# 05_-_Power_Supply.net
KiCad netlist of a schematic drawn in Altium Designer
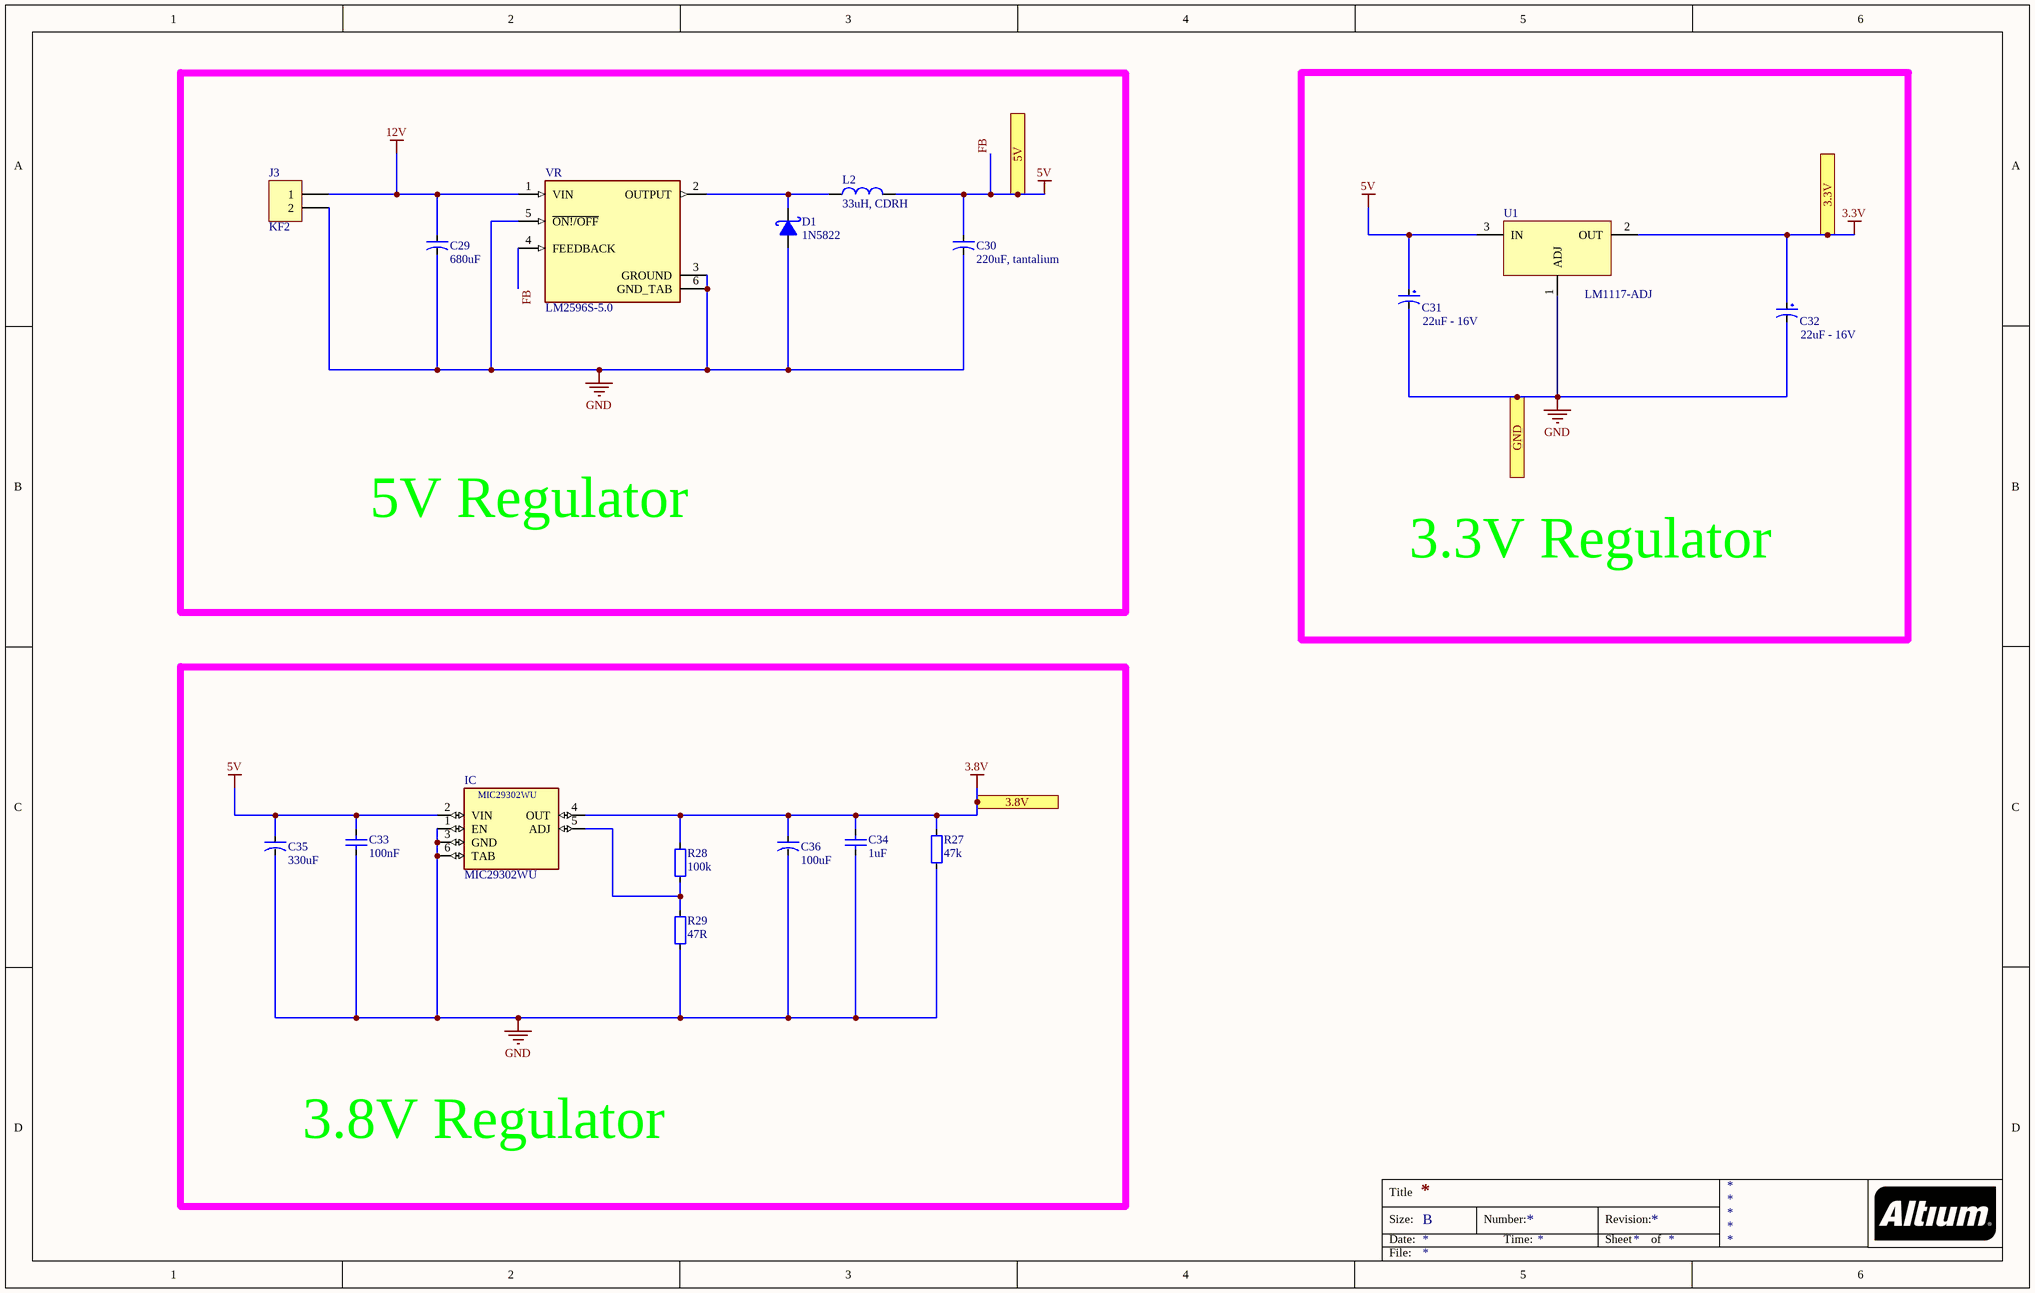
[diagram p0: [05] - Power Supply.SchDoc]

(export (version "E")
  (design (tool "Eeschema 10.0.6"))
  (components
    (comp (ref "C29")
      (value "680uF")
      (footprint "CAP-ALU-SMD-D")
      (description "Polarized Capacitor (Axial)")
      (fields (field (name "PUBLISHER") "Altium Limited"))
      (libsource (lib "My Library") (part "CAP-ALU-SMD"))
    )
    (comp (ref "C30")
      (value "220uF, tantalium")
      (footprint "CAP-ALU-SMD-D")
      (description "Polarized Capacitor (Axial)")
      (fields (field (name "PUBLISHER") "Altium Limited"))
      (libsource (lib "My Library") (part "CAP-ALU-SMD"))
    )
    (comp (ref "C31")
      (value "22uF - 16V")
      (footprint "CAP-ALU-SMD-D")
      (description "Capacitor ALU SMD")
      (libsource (lib "HS_Lib") (part "Cap_ALU_Smd"))
    )
    (comp (ref "C32")
      (value "22uF - 16V")
      (footprint "CAP-ALU-SMD-D")
      (description "Capacitor ALU SMD")
      (libsource (lib "HS_Lib") (part "Cap_ALU_Smd"))
    )
    (comp (ref "C33")
      (value "100nF")
      (footprint "CAP_0805")
      (description "Capacitor")
      (fields (field (name "PUBLISHER") "Altium Limited"))
      (libsource (lib "My Library") (part "CapSMD"))
    )
    (comp (ref "C34")
      (value "1uF")
      (footprint "CAP_0805")
      (description "Capacitor")
      (fields (field (name "PUBLISHER") "Altium Limited"))
      (libsource (lib "My Library") (part "CapSMD"))
    )
    (comp (ref "C35")
      (value "330uF")
      (footprint "CAP-ALU-SMD-D")
      (description "Polarized Capacitor (Axial)")
      (fields (field (name "PUBLISHER") "Altium Limited"))
      (libsource (lib "My Library") (part "CAP-ALU-SMD"))
    )
    (comp (ref "C36")
      (value "100uF")
      (footprint "CAP-ALU-SMD-D")
      (description "Polarized Capacitor (Axial)")
      (fields (field (name "PUBLISHER") "Altium Limited"))
      (libsource (lib "My Library") (part "CAP-ALU-SMD"))
    )
    (comp (ref "D1")
      (value "1N5822")
      (footprint "B560C-13-F")
      (description "Schottky Rectifiers")
      (libsource (lib "My Library") (part "1N5822"))
    )
    (comp (ref "IC")
      (value "MIC29302WU")
      (footprint "TO-263")
      (description "Linear Voltage Regulator IC 1 Output 3A TO-263-5")
      (fields (field (name "MF") "Microchip Technology"))
      (libsource (lib "My Library") (part "MIC29302WU"))
    )
    (comp (ref "J3")
      (value "KF2")
      (footprint "KF2-7.62")
      (fields
        (field (name "MANUFACTURER") "Würth Elektronik eiSos GmbH")
        (field (name "PARTNO") "691103110002")
        (field (name "CREATED BY") "Karrer Zheng")
      )
      (libsource (lib "My Library") (part "KF2"))
    )
    (comp (ref "L2")
      (value "33uH, CDRH")
      (footprint "Inductor_SMD")
      (description "Inductor")
      (libsource (lib "My Library") (part "L1"))
    )
    (comp (ref "R27")
      (value "47k")
      (footprint "RES-SMD-0603")
      (description "Resistor")
      (fields
        (field (name "MANUFACTURER") "Generic Components")
        (field (name "PUBLISHER") "Altium Hobart Technology Centre")
      )
      (libsource (lib "HS_Lib") (part "Resistor - SMD"))
    )
    (comp (ref "R28")
      (value "100k")
      (footprint "RES-SMD-0603")
      (description "Resistor")
      (fields
        (field (name "MANUFACTURER") "Generic Components")
        (field (name "PUBLISHER") "Altium Hobart Technology Centre")
      )
      (libsource (lib "HS_Lib") (part "Resistor - SMD"))
    )
    (comp (ref "R29")
      (value "47R")
      (footprint "RES-SMD-0603")
      (description "Resistor")
      (fields
        (field (name "MANUFACTURER") "Generic Components")
        (field (name "PUBLISHER") "Altium Hobart Technology Centre")
      )
      (libsource (lib "HS_Lib") (part "Resistor - SMD"))
    )
    (comp (ref "U1")
      (value "LM1117-ADJ")
      (footprint "LM1117-SOP")
      (description "800mA Low-Dropout Linear Regulator")
      (fields (field (name "CREATOR") "Nguyen Ba Bien"))
      (libsource (lib "My Library") (part "LM1117-ADJ"))
    )
    (comp (ref "VR")
      (value "LM2596S-5.0")
      (footprint "TO170P1524X483-6N")
      (description "SIMPLE SWITCHER&reg; 4.5V to 40V, 3A Low Component Count Step-Down Regulator 5-DDPAK/TO-263")
      (fields (field (name "MF") "Texas Instruments") (field (name "MP") "LM2596S-5.0/NOPB"))
      (libsource (lib "My Library") (part "LM2596S-5.0"))
    )
  )
  (nets
    (net (code "1") (name "3.3V") (class "Default")
      (node (ref "C32") (pin "1") (pinfunction "1_1") (pintype "passive"))
      (node (ref "U1") (pin "2") (pinfunction "OUT_2") (pintype "passive"))
    )
    (net (code "2") (name "3.8V") (class "Default")
      (node (ref "C34") (pin "2") (pinfunction "2_2") (pintype "passive"))
      (node (ref "C36") (pin "1") (pinfunction "1_1") (pintype "passive"))
      (node (ref "IC") (pin "4") (pinfunction "OUT_4") (pintype "bidirectional"))
      (node (ref "R27") (pin "2") (pinfunction "2_2") (pintype "passive"))
      (node (ref "R28") (pin "2") (pinfunction "2_2") (pintype "passive"))
    )
    (net (code "3") (name "5V") (class "Default")
      (node (ref "C30") (pin "1") (pinfunction "1_1") (pintype "passive"))
      (node (ref "C31") (pin "1") (pinfunction "1_1") (pintype "passive"))
      (node (ref "C33") (pin "2") (pinfunction "2_2") (pintype "passive"))
      (node (ref "C35") (pin "1") (pinfunction "1_1") (pintype "passive"))
      (node (ref "IC") (pin "2") (pinfunction "VIN_2") (pintype "bidirectional"))
      (node (ref "L2") (pin "2") (pinfunction "2_2") (pintype "passive"))
      (node (ref "U1") (pin "3") (pinfunction "IN_3") (pintype "passive"))
      (node (ref "VR") (pin "4") (pinfunction "FEEDBACK_4") (pintype "input"))
    )
    (net (code "4") (name "12V") (class "Default")
      (node (ref "C29") (pin "1") (pinfunction "1_1") (pintype "passive"))
      (node (ref "J3") (pin "1") (pinfunction "1_1") (pintype "passive"))
      (node (ref "VR") (pin "1") (pinfunction "VIN_1") (pintype "input"))
    )
    (net (code "5") (name "GND") (class "Default")
      (node (ref "C29") (pin "2") (pinfunction "2_2") (pintype "passive"))
      (node (ref "C30") (pin "2") (pinfunction "2_2") (pintype "passive"))
      (node (ref "C31") (pin "2") (pinfunction "2_2") (pintype "passive"))
      (node (ref "C32") (pin "2") (pinfunction "2_2") (pintype "passive"))
      (node (ref "C33") (pin "1") (pinfunction "1_1") (pintype "passive"))
      (node (ref "C34") (pin "1") (pinfunction "1_1") (pintype "passive"))
      (node (ref "C35") (pin "2") (pinfunction "2_2") (pintype "passive"))
      (node (ref "C36") (pin "2") (pinfunction "2_2") (pintype "passive"))
      (node (ref "D1") (pin "1") (pinfunction "A_1") (pintype "passive"))
      (node (ref "IC") (pin "1") (pinfunction "EN_1") (pintype "bidirectional"))
      (node (ref "IC") (pin "3") (pinfunction "GND_3") (pintype "bidirectional"))
      (node (ref "IC") (pin "6") (pinfunction "TAB_6") (pintype "bidirectional"))
      (node (ref "J3") (pin "2") (pinfunction "2_2") (pintype "passive"))
      (node (ref "R27") (pin "1") (pinfunction "1_1") (pintype "passive"))
      (node (ref "R29") (pin "1") (pinfunction "1_1") (pintype "passive"))
      (node (ref "U1") (pin "1") (pinfunction "ADJ_1") (pintype "passive"))
      (node (ref "VR") (pin "3") (pinfunction "GROUND_3") (pintype "power_in"))
      (node (ref "VR") (pin "5") (pinfunction "~{ON!/OFF}_5") (pintype "input"))
      (node (ref "VR") (pin "6") (pinfunction "GND_TAB_6") (pintype "power_in"))
    )
    (net (code "6") (name "Net-(D1-K)") (class "Default")
      (node (ref "D1") (pin "2") (pinfunction "K_2") (pintype "passive"))
      (node (ref "L2") (pin "1") (pinfunction "1_1") (pintype "passive"))
      (node (ref "VR") (pin "2") (pinfunction "OUTPUT_2") (pintype "output"))
    )
    (net (code "7") (name "Net-(IC-ADJ)") (class "Default")
      (node (ref "IC") (pin "5") (pinfunction "ADJ_5") (pintype "bidirectional"))
      (node (ref "R28") (pin "1") (pinfunction "1_1") (pintype "passive"))
      (node (ref "R29") (pin "2") (pinfunction "2_2") (pintype "passive"))
    )
  )
)
